# 16_ch_sample-and-hold_card_-_2.net
KiCad netlist of a schematic drawn in EAGLE
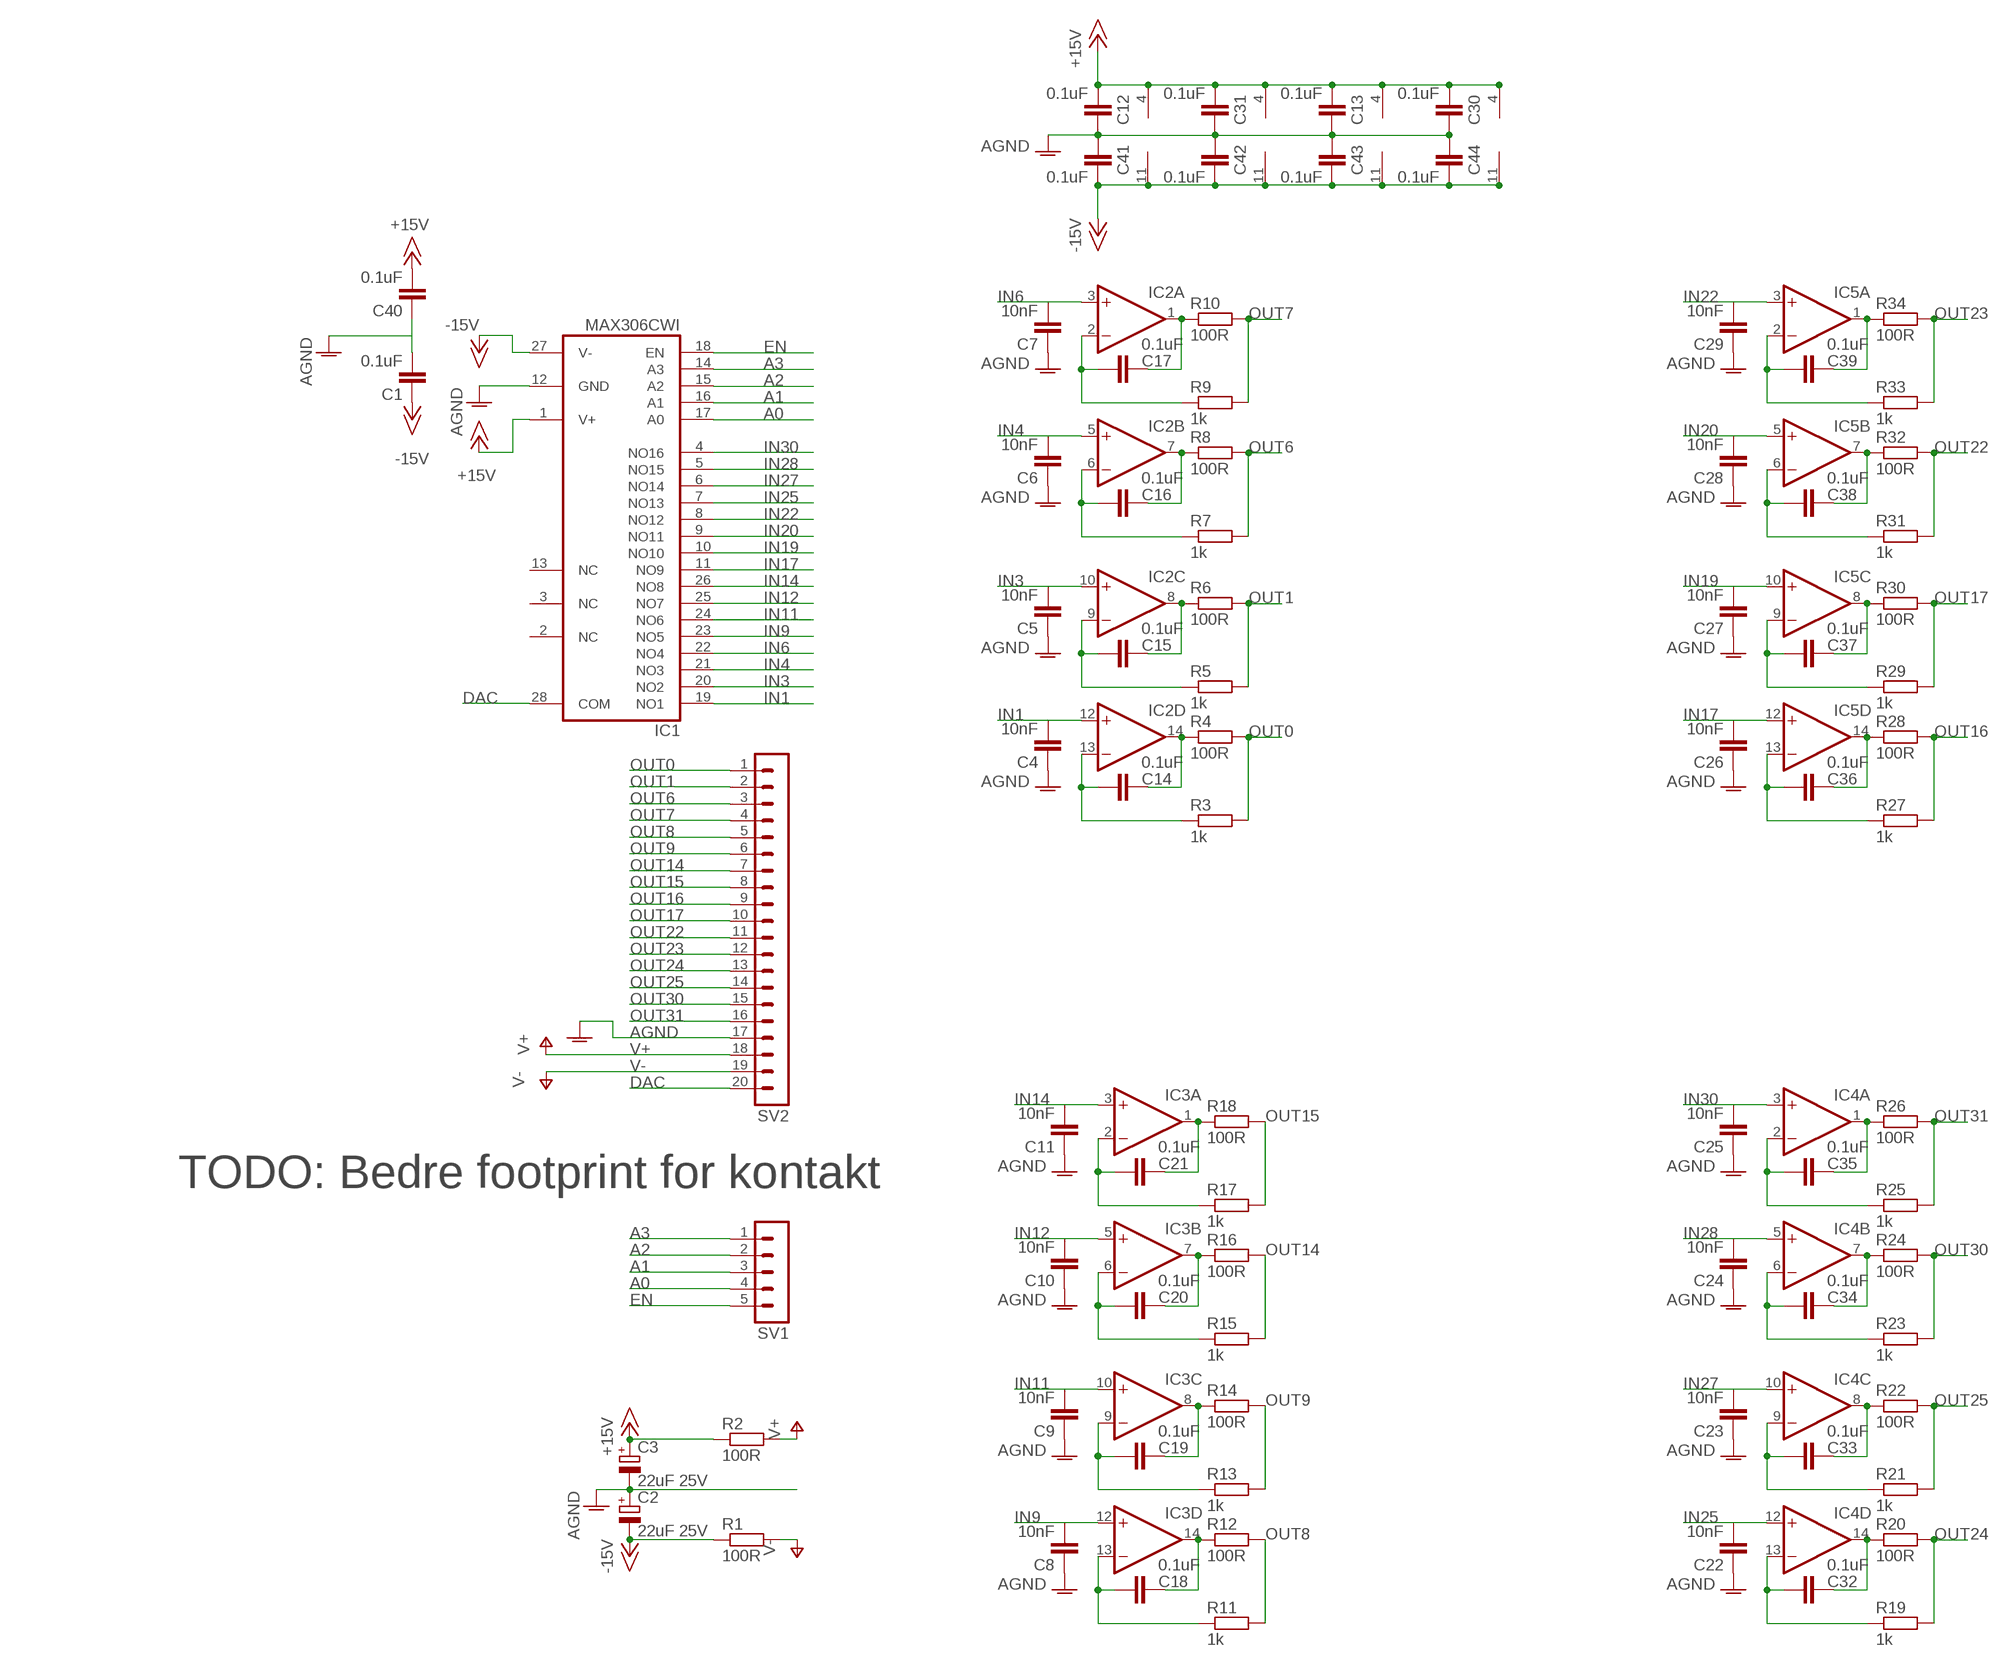
[diagram p0: schematic, sheet 1]

(export (version "E")
  (design (tool "Eeschema 10.0.6"))
  (components
    (comp (ref "C1")
      (value "0.1uF")
      (footprint "eagle-import:C0603")
      (libsource (lib "eagle-import") (part "C-EUC0603"))
    )
    (comp (ref "C2")
      (value "22uF 25V")
      (footprint "eagle-import:E2-5")
      (libsource (lib "eagle-import") (part "CPOL-EUE2-5"))
    )
    (comp (ref "C3")
      (value "22uF 25V")
      (footprint "eagle-import:E2-5")
      (libsource (lib "eagle-import") (part "CPOL-EUE2-5"))
    )
    (comp (ref "C4")
      (value "10nF")
      (footprint "eagle-import:C1206")
      (libsource (lib "eagle-import") (part "C-EUC1206"))
    )
    (comp (ref "C5")
      (value "10nF")
      (footprint "eagle-import:C1206")
      (libsource (lib "eagle-import") (part "C-EUC1206"))
    )
    (comp (ref "C6")
      (value "10nF")
      (footprint "eagle-import:C1206")
      (libsource (lib "eagle-import") (part "C-EUC1206"))
    )
    (comp (ref "C7")
      (value "10nF")
      (footprint "eagle-import:C1206")
      (libsource (lib "eagle-import") (part "C-EUC1206"))
    )
    (comp (ref "C8")
      (value "10nF")
      (footprint "eagle-import:C1206")
      (libsource (lib "eagle-import") (part "C-EUC1206"))
    )
    (comp (ref "C9")
      (value "10nF")
      (footprint "eagle-import:C1206")
      (libsource (lib "eagle-import") (part "C-EUC1206"))
    )
    (comp (ref "C10")
      (value "10nF")
      (footprint "eagle-import:C1206")
      (libsource (lib "eagle-import") (part "C-EUC1206"))
    )
    (comp (ref "C11")
      (value "10nF")
      (footprint "eagle-import:C1206")
      (libsource (lib "eagle-import") (part "C-EUC1206"))
    )
    (comp (ref "C12")
      (value "0.1uF")
      (footprint "eagle-import:C0603")
      (libsource (lib "eagle-import") (part "C-EUC0603"))
    )
    (comp (ref "C13")
      (value "0.1uF")
      (footprint "eagle-import:C0603")
      (libsource (lib "eagle-import") (part "C-EUC0603"))
    )
    (comp (ref "C14")
      (value "0.1uF")
      (footprint "eagle-import:C0603")
      (libsource (lib "eagle-import") (part "C-EUC0603"))
    )
    (comp (ref "C15")
      (value "0.1uF")
      (footprint "eagle-import:C0603")
      (libsource (lib "eagle-import") (part "C-EUC0603"))
    )
    (comp (ref "C16")
      (value "0.1uF")
      (footprint "eagle-import:C0603")
      (libsource (lib "eagle-import") (part "C-EUC0603"))
    )
    (comp (ref "C17")
      (value "0.1uF")
      (footprint "eagle-import:C0603")
      (libsource (lib "eagle-import") (part "C-EUC0603"))
    )
    (comp (ref "C18")
      (value "0.1uF")
      (footprint "eagle-import:C0603")
      (libsource (lib "eagle-import") (part "C-EUC0603"))
    )
    (comp (ref "C19")
      (value "0.1uF")
      (footprint "eagle-import:C0603")
      (libsource (lib "eagle-import") (part "C-EUC0603"))
    )
    (comp (ref "C20")
      (value "0.1uF")
      (footprint "eagle-import:C0603")
      (libsource (lib "eagle-import") (part "C-EUC0603"))
    )
    (comp (ref "C21")
      (value "0.1uF")
      (footprint "eagle-import:C0603")
      (libsource (lib "eagle-import") (part "C-EUC0603"))
    )
    (comp (ref "C22")
      (value "10nF")
      (footprint "eagle-import:C1206")
      (libsource (lib "eagle-import") (part "C-EUC1206"))
    )
    (comp (ref "C23")
      (value "10nF")
      (footprint "eagle-import:C1206")
      (libsource (lib "eagle-import") (part "C-EUC1206"))
    )
    (comp (ref "C24")
      (value "10nF")
      (footprint "eagle-import:C1206")
      (libsource (lib "eagle-import") (part "C-EUC1206"))
    )
    (comp (ref "C25")
      (value "10nF")
      (footprint "eagle-import:C1206")
      (libsource (lib "eagle-import") (part "C-EUC1206"))
    )
    (comp (ref "C26")
      (value "10nF")
      (footprint "eagle-import:C1206")
      (libsource (lib "eagle-import") (part "C-EUC1206"))
    )
    (comp (ref "C27")
      (value "10nF")
      (footprint "eagle-import:C1206")
      (libsource (lib "eagle-import") (part "C-EUC1206"))
    )
    (comp (ref "C28")
      (value "10nF")
      (footprint "eagle-import:C1206")
      (libsource (lib "eagle-import") (part "C-EUC1206"))
    )
    (comp (ref "C29")
      (value "10nF")
      (footprint "eagle-import:C1206")
      (libsource (lib "eagle-import") (part "C-EUC1206"))
    )
    (comp (ref "C30")
      (value "0.1uF")
      (footprint "eagle-import:C0603")
      (libsource (lib "eagle-import") (part "C-EUC0603"))
    )
    (comp (ref "C31")
      (value "0.1uF")
      (footprint "eagle-import:C0603")
      (libsource (lib "eagle-import") (part "C-EUC0603"))
    )
    (comp (ref "C32")
      (value "0.1uF")
      (footprint "eagle-import:C0603")
      (libsource (lib "eagle-import") (part "C-EUC0603"))
    )
    (comp (ref "C33")
      (value "0.1uF")
      (footprint "eagle-import:C0603")
      (libsource (lib "eagle-import") (part "C-EUC0603"))
    )
    (comp (ref "C34")
      (value "0.1uF")
      (footprint "eagle-import:C0603")
      (libsource (lib "eagle-import") (part "C-EUC0603"))
    )
    (comp (ref "C35")
      (value "0.1uF")
      (footprint "eagle-import:C0603")
      (libsource (lib "eagle-import") (part "C-EUC0603"))
    )
    (comp (ref "C36")
      (value "0.1uF")
      (footprint "eagle-import:C0603")
      (libsource (lib "eagle-import") (part "C-EUC0603"))
    )
    (comp (ref "C37")
      (value "0.1uF")
      (footprint "eagle-import:C0603")
      (libsource (lib "eagle-import") (part "C-EUC0603"))
    )
    (comp (ref "C38")
      (value "0.1uF")
      (footprint "eagle-import:C0603")
      (libsource (lib "eagle-import") (part "C-EUC0603"))
    )
    (comp (ref "C39")
      (value "0.1uF")
      (footprint "eagle-import:C0603")
      (libsource (lib "eagle-import") (part "C-EUC0603"))
    )
    (comp (ref "C40")
      (value "0.1uF")
      (footprint "eagle-import:C0603")
      (libsource (lib "eagle-import") (part "C-EUC0603"))
    )
    (comp (ref "C41")
      (value "0.1uF")
      (footprint "eagle-import:C0603")
      (libsource (lib "eagle-import") (part "C-EUC0603"))
    )
    (comp (ref "C42")
      (value "0.1uF")
      (footprint "eagle-import:C0603")
      (libsource (lib "eagle-import") (part "C-EUC0603"))
    )
    (comp (ref "C43")
      (value "0.1uF")
      (footprint "eagle-import:C0603")
      (libsource (lib "eagle-import") (part "C-EUC0603"))
    )
    (comp (ref "C44")
      (value "0.1uF")
      (footprint "eagle-import:C0603")
      (libsource (lib "eagle-import") (part "C-EUC0603"))
    )
    (comp (ref "IC1")
      (value "MAX306CWI")
      (footprint "eagle-import:SO28L")
      (fields (field (name "MF") "MAXIM"))
      (libsource (lib "eagle-import") (part "MAX306CWI"))
    )
    (comp (ref "IC2")
      (value "TL074D")
      (footprint "eagle-import:SO14")
      (libsource (lib "eagle-import") (part "TL074D"))
    )
    (comp (ref "IC3")
      (value "TL074D")
      (footprint "eagle-import:SO14")
      (libsource (lib "eagle-import") (part "TL074D"))
    )
    (comp (ref "IC4")
      (value "TL074D")
      (footprint "eagle-import:SO14")
      (libsource (lib "eagle-import") (part "TL074D"))
    )
    (comp (ref "IC5")
      (value "TL074D")
      (footprint "eagle-import:SO14")
      (libsource (lib "eagle-import") (part "TL074D"))
    )
    (comp (ref "R1")
      (value "100R")
      (footprint "eagle-import:0207_7")
      (libsource (lib "eagle-import") (part "R-EU_0207/7"))
    )
    (comp (ref "R2")
      (value "100R")
      (footprint "eagle-import:0207_7")
      (libsource (lib "eagle-import") (part "R-EU_0207/7"))
    )
    (comp (ref "R3")
      (value "1k")
      (footprint "eagle-import:R0603")
      (libsource (lib "eagle-import") (part "R-EU_R0603"))
    )
    (comp (ref "R4")
      (value "100R")
      (footprint "eagle-import:R0603")
      (libsource (lib "eagle-import") (part "R-EU_R0603"))
    )
    (comp (ref "R5")
      (value "1k")
      (footprint "eagle-import:R0603")
      (libsource (lib "eagle-import") (part "R-EU_R0603"))
    )
    (comp (ref "R6")
      (value "100R")
      (footprint "eagle-import:R0603")
      (libsource (lib "eagle-import") (part "R-EU_R0603"))
    )
    (comp (ref "R7")
      (value "1k")
      (footprint "eagle-import:R0603")
      (libsource (lib "eagle-import") (part "R-EU_R0603"))
    )
    (comp (ref "R8")
      (value "100R")
      (footprint "eagle-import:R0603")
      (libsource (lib "eagle-import") (part "R-EU_R0603"))
    )
    (comp (ref "R9")
      (value "1k")
      (footprint "eagle-import:R0603")
      (libsource (lib "eagle-import") (part "R-EU_R0603"))
    )
    (comp (ref "R10")
      (value "100R")
      (footprint "eagle-import:R0603")
      (libsource (lib "eagle-import") (part "R-EU_R0603"))
    )
    (comp (ref "R11")
      (value "1k")
      (footprint "eagle-import:R0603")
      (libsource (lib "eagle-import") (part "R-EU_R0603"))
    )
    (comp (ref "R12")
      (value "100R")
      (footprint "eagle-import:R0603")
      (libsource (lib "eagle-import") (part "R-EU_R0603"))
    )
    (comp (ref "R13")
      (value "1k")
      (footprint "eagle-import:R0603")
      (libsource (lib "eagle-import") (part "R-EU_R0603"))
    )
    (comp (ref "R14")
      (value "100R")
      (footprint "eagle-import:R0603")
      (libsource (lib "eagle-import") (part "R-EU_R0603"))
    )
    (comp (ref "R15")
      (value "1k")
      (footprint "eagle-import:R0603")
      (libsource (lib "eagle-import") (part "R-EU_R0603"))
    )
    (comp (ref "R16")
      (value "100R")
      (footprint "eagle-import:R0603")
      (libsource (lib "eagle-import") (part "R-EU_R0603"))
    )
    (comp (ref "R17")
      (value "1k")
      (footprint "eagle-import:R0603")
      (libsource (lib "eagle-import") (part "R-EU_R0603"))
    )
    (comp (ref "R18")
      (value "100R")
      (footprint "eagle-import:R0603")
      (libsource (lib "eagle-import") (part "R-EU_R0603"))
    )
    (comp (ref "R19")
      (value "1k")
      (footprint "eagle-import:R0603")
      (libsource (lib "eagle-import") (part "R-EU_R0603"))
    )
    (comp (ref "R20")
      (value "100R")
      (footprint "eagle-import:R0603")
      (libsource (lib "eagle-import") (part "R-EU_R0603"))
    )
    (comp (ref "R21")
      (value "1k")
      (footprint "eagle-import:R0603")
      (libsource (lib "eagle-import") (part "R-EU_R0603"))
    )
    (comp (ref "R22")
      (value "100R")
      (footprint "eagle-import:R0603")
      (libsource (lib "eagle-import") (part "R-EU_R0603"))
    )
    (comp (ref "R23")
      (value "1k")
      (footprint "eagle-import:R0603")
      (libsource (lib "eagle-import") (part "R-EU_R0603"))
    )
    (comp (ref "R24")
      (value "100R")
      (footprint "eagle-import:R0603")
      (libsource (lib "eagle-import") (part "R-EU_R0603"))
    )
    (comp (ref "R25")
      (value "1k")
      (footprint "eagle-import:R0603")
      (libsource (lib "eagle-import") (part "R-EU_R0603"))
    )
    (comp (ref "R26")
      (value "100R")
      (footprint "eagle-import:R0603")
      (libsource (lib "eagle-import") (part "R-EU_R0603"))
    )
    (comp (ref "R27")
      (value "1k")
      (footprint "eagle-import:R0603")
      (libsource (lib "eagle-import") (part "R-EU_R0603"))
    )
    (comp (ref "R28")
      (value "100R")
      (footprint "eagle-import:R0603")
      (libsource (lib "eagle-import") (part "R-EU_R0603"))
    )
    (comp (ref "R29")
      (value "1k")
      (footprint "eagle-import:R0603")
      (libsource (lib "eagle-import") (part "R-EU_R0603"))
    )
    (comp (ref "R30")
      (value "100R")
      (footprint "eagle-import:R0603")
      (libsource (lib "eagle-import") (part "R-EU_R0603"))
    )
    (comp (ref "R31")
      (value "1k")
      (footprint "eagle-import:R0603")
      (libsource (lib "eagle-import") (part "R-EU_R0603"))
    )
    (comp (ref "R32")
      (value "100R")
      (footprint "eagle-import:R0603")
      (libsource (lib "eagle-import") (part "R-EU_R0603"))
    )
    (comp (ref "R33")
      (value "1k")
      (footprint "eagle-import:R0603")
      (libsource (lib "eagle-import") (part "R-EU_R0603"))
    )
    (comp (ref "R34")
      (value "100R")
      (footprint "eagle-import:R0603")
      (libsource (lib "eagle-import") (part "R-EU_R0603"))
    )
    (comp (ref "SV1")
      (value "MA05-1")
      (footprint "eagle-import:MA05-1")
      (libsource (lib "eagle-import") (part "MA05-1"))
    )
    (comp (ref "SV2")
      (value "MA20-1")
      (footprint "eagle-import:MA20-1")
      (libsource (lib "eagle-import") (part "MA20-1"))
    )
  )
  (nets
    (net (code "1") (name "+15V") (class "Default")
      (node (ref "C12") (pin "1") (pinfunction "1_1") (pintype "passive"))
      (node (ref "C13") (pin "1") (pinfunction "1_1") (pintype "passive"))
      (node (ref "C3") (pin "+") (pinfunction "+_+") (pintype "passive"))
      (node (ref "C30") (pin "1") (pinfunction "1_1") (pintype "passive"))
      (node (ref "C31") (pin "1") (pinfunction "1_1") (pintype "passive"))
      (node (ref "C40") (pin "2") (pinfunction "2_2") (pintype "passive"))
      (node (ref "IC1") (pin "1") (pinfunction "V+_1") (pintype "power_in"))
      (node (ref "IC2") (pin "4") (pinfunction "V+_4") (pintype "power_in"))
      (node (ref "IC3") (pin "4") (pinfunction "V+_4") (pintype "power_in"))
      (node (ref "IC4") (pin "4") (pinfunction "V+_4") (pintype "power_in"))
      (node (ref "IC5") (pin "4") (pinfunction "V+_4") (pintype "power_in"))
      (node (ref "R2") (pin "1") (pinfunction "1_1") (pintype "passive"))
    )
    (net (code "2") (name "-15V") (class "Default")
      (node (ref "C1") (pin "1") (pinfunction "1_1") (pintype "passive"))
      (node (ref "C2") (pin "-") (pinfunction "-_-") (pintype "passive"))
      (node (ref "C41") (pin "2") (pinfunction "2_2") (pintype "passive"))
      (node (ref "C42") (pin "2") (pinfunction "2_2") (pintype "passive"))
      (node (ref "C43") (pin "2") (pinfunction "2_2") (pintype "passive"))
      (node (ref "C44") (pin "2") (pinfunction "2_2") (pintype "passive"))
      (node (ref "IC1") (pin "27") (pinfunction "V-_27") (pintype "power_in"))
      (node (ref "IC2") (pin "11") (pinfunction "V-_11") (pintype "power_in"))
      (node (ref "IC3") (pin "11") (pinfunction "V-_11") (pintype "power_in"))
      (node (ref "IC4") (pin "11") (pinfunction "V-_11") (pintype "power_in"))
      (node (ref "IC5") (pin "11") (pinfunction "V-_11") (pintype "power_in"))
      (node (ref "R1") (pin "1") (pinfunction "1_1") (pintype "passive"))
    )
    (net (code "3") (name "/A0") (class "Default")
      (node (ref "IC1") (pin "17") (pinfunction "A0_17") (pintype "input"))
      (node (ref "SV1") (pin "4") (pinfunction "4_4") (pintype "passive"))
    )
    (net (code "4") (name "/A1") (class "Default")
      (node (ref "IC1") (pin "16") (pinfunction "A1_16") (pintype "input"))
      (node (ref "SV1") (pin "3") (pinfunction "3_3") (pintype "passive"))
    )
    (net (code "5") (name "/A2") (class "Default")
      (node (ref "IC1") (pin "15") (pinfunction "A2_15") (pintype "input"))
      (node (ref "SV1") (pin "2") (pinfunction "2_2") (pintype "passive"))
    )
    (net (code "6") (name "/A3") (class "Default")
      (node (ref "IC1") (pin "14") (pinfunction "A3_14") (pintype "input"))
      (node (ref "SV1") (pin "1") (pinfunction "1_1") (pintype "passive"))
    )
    (net (code "7") (name "/DAC") (class "Default")
      (node (ref "IC1") (pin "28") (pinfunction "COM_28") (pintype "passive"))
      (node (ref "SV2") (pin "20") (pinfunction "20_20") (pintype "passive"))
    )
    (net (code "8") (name "/EN") (class "Default")
      (node (ref "IC1") (pin "18") (pinfunction "EN_18") (pintype "input"))
      (node (ref "SV1") (pin "5") (pinfunction "5_5") (pintype "passive"))
    )
    (net (code "9") (name "/IN1") (class "Default")
      (node (ref "C4") (pin "2") (pinfunction "2_2") (pintype "passive"))
      (node (ref "IC1") (pin "19") (pinfunction "NO1_19") (pintype "passive"))
      (node (ref "IC2") (pin "12") (pinfunction "+IN_12") (pintype "input"))
    )
    (net (code "10") (name "/IN3") (class "Default")
      (node (ref "C5") (pin "2") (pinfunction "2_2") (pintype "passive"))
      (node (ref "IC1") (pin "20") (pinfunction "NO2_20") (pintype "passive"))
      (node (ref "IC2") (pin "10") (pinfunction "+IN_10") (pintype "input"))
    )
    (net (code "11") (name "/IN4") (class "Default")
      (node (ref "C6") (pin "2") (pinfunction "2_2") (pintype "passive"))
      (node (ref "IC1") (pin "21") (pinfunction "NO3_21") (pintype "passive"))
      (node (ref "IC2") (pin "5") (pinfunction "+IN_5") (pintype "input"))
    )
    (net (code "12") (name "/IN6") (class "Default")
      (node (ref "C7") (pin "2") (pinfunction "2_2") (pintype "passive"))
      (node (ref "IC1") (pin "22") (pinfunction "NO4_22") (pintype "passive"))
      (node (ref "IC2") (pin "3") (pinfunction "+IN_3") (pintype "input"))
    )
    (net (code "13") (name "/IN9") (class "Default")
      (node (ref "C8") (pin "2") (pinfunction "2_2") (pintype "passive"))
      (node (ref "IC1") (pin "23") (pinfunction "NO5_23") (pintype "passive"))
      (node (ref "IC3") (pin "12") (pinfunction "+IN_12") (pintype "input"))
    )
    (net (code "14") (name "/IN11") (class "Default")
      (node (ref "C9") (pin "2") (pinfunction "2_2") (pintype "passive"))
      (node (ref "IC1") (pin "24") (pinfunction "NO6_24") (pintype "passive"))
      (node (ref "IC3") (pin "10") (pinfunction "+IN_10") (pintype "input"))
    )
    (net (code "15") (name "/IN12") (class "Default")
      (node (ref "C10") (pin "2") (pinfunction "2_2") (pintype "passive"))
      (node (ref "IC1") (pin "25") (pinfunction "NO7_25") (pintype "passive"))
      (node (ref "IC3") (pin "5") (pinfunction "+IN_5") (pintype "input"))
    )
    (net (code "16") (name "/IN14") (class "Default")
      (node (ref "C11") (pin "2") (pinfunction "2_2") (pintype "passive"))
      (node (ref "IC1") (pin "26") (pinfunction "NO8_26") (pintype "passive"))
      (node (ref "IC3") (pin "3") (pinfunction "+IN_3") (pintype "input"))
    )
    (net (code "17") (name "/IN17") (class "Default")
      (node (ref "C26") (pin "2") (pinfunction "2_2") (pintype "passive"))
      (node (ref "IC1") (pin "11") (pinfunction "NO9_11") (pintype "passive"))
      (node (ref "IC5") (pin "12") (pinfunction "+IN_12") (pintype "input"))
    )
    (net (code "18") (name "/IN19") (class "Default")
      (node (ref "C27") (pin "2") (pinfunction "2_2") (pintype "passive"))
      (node (ref "IC1") (pin "10") (pinfunction "NO10_10") (pintype "passive"))
      (node (ref "IC5") (pin "10") (pinfunction "+IN_10") (pintype "input"))
    )
    (net (code "19") (name "/IN20") (class "Default")
      (node (ref "C28") (pin "2") (pinfunction "2_2") (pintype "passive"))
      (node (ref "IC1") (pin "9") (pinfunction "NO11_9") (pintype "passive"))
      (node (ref "IC5") (pin "5") (pinfunction "+IN_5") (pintype "input"))
    )
    (net (code "20") (name "/IN22") (class "Default")
      (node (ref "C29") (pin "2") (pinfunction "2_2") (pintype "passive"))
      (node (ref "IC1") (pin "8") (pinfunction "NO12_8") (pintype "passive"))
      (node (ref "IC5") (pin "3") (pinfunction "+IN_3") (pintype "input"))
    )
    (net (code "21") (name "/IN25") (class "Default")
      (node (ref "C22") (pin "2") (pinfunction "2_2") (pintype "passive"))
      (node (ref "IC1") (pin "7") (pinfunction "NO13_7") (pintype "passive"))
      (node (ref "IC4") (pin "12") (pinfunction "+IN_12") (pintype "input"))
    )
    (net (code "22") (name "/IN27") (class "Default")
      (node (ref "C23") (pin "2") (pinfunction "2_2") (pintype "passive"))
      (node (ref "IC1") (pin "6") (pinfunction "NO14_6") (pintype "passive"))
      (node (ref "IC4") (pin "10") (pinfunction "+IN_10") (pintype "input"))
    )
    (net (code "23") (name "/IN28") (class "Default")
      (node (ref "C24") (pin "2") (pinfunction "2_2") (pintype "passive"))
      (node (ref "IC1") (pin "5") (pinfunction "NO15_5") (pintype "passive"))
      (node (ref "IC4") (pin "5") (pinfunction "+IN_5") (pintype "input"))
    )
    (net (code "24") (name "/IN30") (class "Default")
      (node (ref "C25") (pin "2") (pinfunction "2_2") (pintype "passive"))
      (node (ref "IC1") (pin "4") (pinfunction "NO16_4") (pintype "passive"))
      (node (ref "IC4") (pin "3") (pinfunction "+IN_3") (pintype "input"))
    )
    (net (code "25") (name "/OUT0") (class "Default")
      (node (ref "R3") (pin "2") (pinfunction "2_2") (pintype "passive"))
      (node (ref "R4") (pin "2") (pinfunction "2_2") (pintype "passive"))
      (node (ref "SV2") (pin "1") (pinfunction "1_1") (pintype "passive"))
    )
    (net (code "26") (name "/OUT1") (class "Default")
      (node (ref "R5") (pin "2") (pinfunction "2_2") (pintype "passive"))
      (node (ref "R6") (pin "2") (pinfunction "2_2") (pintype "passive"))
      (node (ref "SV2") (pin "2") (pinfunction "2_2") (pintype "passive"))
    )
    (net (code "27") (name "/OUT6") (class "Default")
      (node (ref "R7") (pin "2") (pinfunction "2_2") (pintype "passive"))
      (node (ref "R8") (pin "2") (pinfunction "2_2") (pintype "passive"))
      (node (ref "SV2") (pin "3") (pinfunction "3_3") (pintype "passive"))
    )
    (net (code "28") (name "/OUT7") (class "Default")
      (node (ref "R10") (pin "2") (pinfunction "2_2") (pintype "passive"))
      (node (ref "R9") (pin "2") (pinfunction "2_2") (pintype "passive"))
      (node (ref "SV2") (pin "4") (pinfunction "4_4") (pintype "passive"))
    )
    (net (code "29") (name "/OUT8") (class "Default")
      (node (ref "R11") (pin "2") (pinfunction "2_2") (pintype "passive"))
      (node (ref "R12") (pin "2") (pinfunction "2_2") (pintype "passive"))
      (node (ref "SV2") (pin "5") (pinfunction "5_5") (pintype "passive"))
    )
    (net (code "30") (name "/OUT9") (class "Default")
      (node (ref "R13") (pin "2") (pinfunction "2_2") (pintype "passive"))
      (node (ref "R14") (pin "2") (pinfunction "2_2") (pintype "passive"))
      (node (ref "SV2") (pin "6") (pinfunction "6_6") (pintype "passive"))
    )
    (net (code "31") (name "/OUT14") (class "Default")
      (node (ref "R15") (pin "2") (pinfunction "2_2") (pintype "passive"))
      (node (ref "R16") (pin "2") (pinfunction "2_2") (pintype "passive"))
      (node (ref "SV2") (pin "7") (pinfunction "7_7") (pintype "passive"))
    )
    (net (code "32") (name "/OUT15") (class "Default")
      (node (ref "R17") (pin "2") (pinfunction "2_2") (pintype "passive"))
      (node (ref "R18") (pin "2") (pinfunction "2_2") (pintype "passive"))
      (node (ref "SV2") (pin "8") (pinfunction "8_8") (pintype "passive"))
    )
    (net (code "33") (name "/OUT16") (class "Default")
      (node (ref "R27") (pin "2") (pinfunction "2_2") (pintype "passive"))
      (node (ref "R28") (pin "2") (pinfunction "2_2") (pintype "passive"))
      (node (ref "SV2") (pin "9") (pinfunction "9_9") (pintype "passive"))
    )
    (net (code "34") (name "/OUT17") (class "Default")
      (node (ref "R29") (pin "2") (pinfunction "2_2") (pintype "passive"))
      (node (ref "R30") (pin "2") (pinfunction "2_2") (pintype "passive"))
      (node (ref "SV2") (pin "10") (pinfunction "10_10") (pintype "passive"))
    )
    (net (code "35") (name "/OUT22") (class "Default")
      (node (ref "R31") (pin "2") (pinfunction "2_2") (pintype "passive"))
      (node (ref "R32") (pin "2") (pinfunction "2_2") (pintype "passive"))
      (node (ref "SV2") (pin "11") (pinfunction "11_11") (pintype "passive"))
    )
    (net (code "36") (name "/OUT23") (class "Default")
      (node (ref "R33") (pin "2") (pinfunction "2_2") (pintype "passive"))
      (node (ref "R34") (pin "2") (pinfunction "2_2") (pintype "passive"))
      (node (ref "SV2") (pin "12") (pinfunction "12_12") (pintype "passive"))
    )
    (net (code "37") (name "/OUT24") (class "Default")
      (node (ref "R19") (pin "2") (pinfunction "2_2") (pintype "passive"))
      (node (ref "R20") (pin "2") (pinfunction "2_2") (pintype "passive"))
      (node (ref "SV2") (pin "13") (pinfunction "13_13") (pintype "passive"))
    )
    (net (code "38") (name "/OUT25") (class "Default")
      (node (ref "R21") (pin "2") (pinfunction "2_2") (pintype "passive"))
      (node (ref "R22") (pin "2") (pinfunction "2_2") (pintype "passive"))
      (node (ref "SV2") (pin "14") (pinfunction "14_14") (pintype "passive"))
    )
    (net (code "39") (name "/OUT30") (class "Default")
      (node (ref "R23") (pin "2") (pinfunction "2_2") (pintype "passive"))
      (node (ref "R24") (pin "2") (pinfunction "2_2") (pintype "passive"))
      (node (ref "SV2") (pin "15") (pinfunction "15_15") (pintype "passive"))
    )
    (net (code "40") (name "/OUT31") (class "Default")
      (node (ref "R25") (pin "2") (pinfunction "2_2") (pintype "passive"))
      (node (ref "R26") (pin "2") (pinfunction "2_2") (pintype "passive"))
      (node (ref "SV2") (pin "16") (pinfunction "16_16") (pintype "passive"))
    )
    (net (code "41") (name "AGND") (class "Default")
      (node (ref "C1") (pin "2") (pinfunction "2_2") (pintype "passive"))
      (node (ref "C10") (pin "1") (pinfunction "1_1") (pintype "passive"))
      (node (ref "C11") (pin "1") (pinfunction "1_1") (pintype "passive"))
      (node (ref "C12") (pin "2") (pinfunction "2_2") (pintype "passive"))
      (node (ref "C13") (pin "2") (pinfunction "2_2") (pintype "passive"))
      (node (ref "C2") (pin "+") (pinfunction "+_+") (pintype "passive"))
      (node (ref "C22") (pin "1") (pinfunction "1_1") (pintype "passive"))
      (node (ref "C23") (pin "1") (pinfunction "1_1") (pintype "passive"))
      (node (ref "C24") (pin "1") (pinfunction "1_1") (pintype "passive"))
      (node (ref "C25") (pin "1") (pinfunction "1_1") (pintype "passive"))
      (node (ref "C26") (pin "1") (pinfunction "1_1") (pintype "passive"))
      (node (ref "C27") (pin "1") (pinfunction "1_1") (pintype "passive"))
      (node (ref "C28") (pin "1") (pinfunction "1_1") (pintype "passive"))
      (node (ref "C29") (pin "1") (pinfunction "1_1") (pintype "passive"))
      (node (ref "C3") (pin "-") (pinfunction "-_-") (pintype "passive"))
      (node (ref "C30") (pin "2") (pinfunction "2_2") (pintype "passive"))
      (node (ref "C31") (pin "2") (pinfunction "2_2") (pintype "passive"))
      (node (ref "C4") (pin "1") (pinfunction "1_1") (pintype "passive"))
      (node (ref "C40") (pin "1") (pinfunction "1_1") (pintype "passive"))
      (node (ref "C41") (pin "1") (pinfunction "1_1") (pintype "passive"))
      (node (ref "C42") (pin "1") (pinfunction "1_1") (pintype "passive"))
      (node (ref "C43") (pin "1") (pinfunction "1_1") (pintype "passive"))
      (node (ref "C44") (pin "1") (pinfunction "1_1") (pintype "passive"))
      (node (ref "C5") (pin "1") (pinfunction "1_1") (pintype "passive"))
      (node (ref "C6") (pin "1") (pinfunction "1_1") (pintype "passive"))
      (node (ref "C7") (pin "1") (pinfunction "1_1") (pintype "passive"))
      (node (ref "C8") (pin "1") (pinfunction "1_1") (pintype "passive"))
      (node (ref "C9") (pin "1") (pinfunction "1_1") (pintype "passive"))
      (node (ref "IC1") (pin "12") (pinfunction "GND_12") (pintype "power_in"))
      (node (ref "SV2") (pin "17") (pinfunction "17_17") (pintype "passive"))
    )
    (net (code "42") (name "Net-(IC2A--IN)") (class "Default")
      (node (ref "C17") (pin "2") (pinfunction "2_2") (pintype "passive"))
      (node (ref "IC2") (pin "2") (pinfunction "-IN_2") (pintype "input"))
      (node (ref "R9") (pin "1") (pinfunction "1_1") (pintype "passive"))
    )
    (net (code "43") (name "Net-(IC2A-OUT)") (class "Default")
      (node (ref "C17") (pin "1") (pinfunction "1_1") (pintype "passive"))
      (node (ref "IC2") (pin "1") (pinfunction "OUT_1") (pintype "output"))
      (node (ref "R10") (pin "1") (pinfunction "1_1") (pintype "passive"))
    )
    (net (code "44") (name "Net-(IC2B--IN)") (class "Default")
      (node (ref "C16") (pin "2") (pinfunction "2_2") (pintype "passive"))
      (node (ref "IC2") (pin "6") (pinfunction "-IN_6") (pintype "input"))
      (node (ref "R7") (pin "1") (pinfunction "1_1") (pintype "passive"))
    )
    (net (code "45") (name "Net-(IC2B-OUT)") (class "Default")
      (node (ref "C16") (pin "1") (pinfunction "1_1") (pintype "passive"))
      (node (ref "IC2") (pin "7") (pinfunction "OUT_7") (pintype "output"))
      (node (ref "R8") (pin "1") (pinfunction "1_1") (pintype "passive"))
    )
    (net (code "46") (name "Net-(IC2C--IN)") (class "Default")
      (node (ref "C15") (pin "2") (pinfunction "2_2") (pintype "passive"))
      (node (ref "IC2") (pin "9") (pinfunction "-IN_9") (pintype "input"))
      (node (ref "R5") (pin "1") (pinfunction "1_1") (pintype "passive"))
    )
    (net (code "47") (name "Net-(IC2C-OUT)") (class "Default")
      (node (ref "C15") (pin "1") (pinfunction "1_1") (pintype "passive"))
      (node (ref "IC2") (pin "8") (pinfunction "OUT_8") (pintype "output"))
      (node (ref "R6") (pin "1") (pinfunction "1_1") (pintype "passive"))
    )
    (net (code "48") (name "Net-(IC2D--IN)") (class "Default")
      (node (ref "C14") (pin "2") (pinfunction "2_2") (pintype "passive"))
      (node (ref "IC2") (pin "13") (pinfunction "-IN_13") (pintype "input"))
      (node (ref "R3") (pin "1") (pinfunction "1_1") (pintype "passive"))
    )
    (net (code "49") (name "Net-(IC2D-OUT)") (class "Default")
      (node (ref "C14") (pin "1") (pinfunction "1_1") (pintype "passive"))
      (node (ref "IC2") (pin "14") (pinfunction "OUT_14") (pintype "output"))
      (node (ref "R4") (pin "1") (pinfunction "1_1") (pintype "passive"))
    )
    (net (code "50") (name "Net-(IC3A--IN)") (class "Default")
      (node (ref "C21") (pin "2") (pinfunction "2_2") (pintype "passive"))
      (node (ref "IC3") (pin "2") (pinfunction "-IN_2") (pintype "input"))
      (node (ref "R17") (pin "1") (pinfunction "1_1") (pintype "passive"))
    )
    (net (code "51") (name "Net-(IC3A-OUT)") (class "Default")
      (node (ref "C21") (pin "1") (pinfunction "1_1") (pintype "passive"))
      (node (ref "IC3") (pin "1") (pinfunction "OUT_1") (pintype "output"))
      (node (ref "R18") (pin "1") (pinfunction "1_1") (pintype "passive"))
    )
    (net (code "52") (name "Net-(IC3B--IN)") (class "Default")
      (node (ref "C20") (pin "2") (pinfunction "2_2") (pintype "passive"))
      (node (ref "IC3") (pin "6") (pinfunction "-IN_6") (pintype "input"))
      (node (ref "R15") (pin "1") (pinfunction "1_1") (pintype "passive"))
    )
    (net (code "53") (name "Net-(IC3B-OUT)") (class "Default")
      (node (ref "C20") (pin "1") (pinfunction "1_1") (pintype "passive"))
      (node (ref "IC3") (pin "7") (pinfunction "OUT_7") (pintype "output"))
      (node (ref "R16") (pin "1") (pinfunction "1_1") (pintype "passive"))
    )
    (net (code "54") (name "Net-(IC3C--IN)") (class "Default")
      (node (ref "C19") (pin "2") (pinfunction "2_2") (pintype "passive"))
      (node (ref "IC3") (pin "9") (pinfunction "-IN_9") (pintype "input"))
      (node (ref "R13") (pin "1") (pinfunction "1_1") (pintype "passive"))
    )
    (net (code "55") (name "Net-(IC3C-OUT)") (class "Default")
      (node (ref "C19") (pin "1") (pinfunction "1_1") (pintype "passive"))
      (node (ref "IC3") (pin "8") (pinfunction "OUT_8") (pintype "output"))
      (node (ref "R14") (pin "1") (pinfunction "1_1") (pintype "passive"))
    )
    (net (code "56") (name "Net-(IC3D--IN)") (class "Default")
      (node (ref "C18") (pin "2") (pinfunction "2_2") (pintype "passive"))
      (node (ref "IC3") (pin "13") (pinfunction "-IN_13") (pintype "input"))
      (node (ref "R11") (pin "1") (pinfunction "1_1") (pintype "passive"))
    )
    (net (code "57") (name "Net-(IC3D-OUT)") (class "Default")
      (node (ref "C18") (pin "1") (pinfunction "1_1") (pintype "passive"))
      (node (ref "IC3") (pin "14") (pinfunction "OUT_14") (pintype "output"))
      (node (ref "R12") (pin "1") (pinfunction "1_1") (pintype "passive"))
    )
    (net (code "58") (name "Net-(IC4A--IN)") (class "Default")
      (node (ref "C35") (pin "2") (pinfunction "2_2") (pintype "passive"))
      (node (ref "IC4") (pin "2") (pinfunction "-IN_2") (pintype "input"))
      (node (ref "R25") (pin "1") (pinfunction "1_1") (pintype "passive"))
    )
    (net (code "59") (name "Net-(IC4A-OUT)") (class "Default")
      (node (ref "C35") (pin "1") (pinfunction "1_1") (pintype "passive"))
      (node (ref "IC4") (pin "1") (pinfunction "OUT_1") (pintype "output"))
      (node (ref "R26") (pin "1") (pinfunction "1_1") (pintype "passive"))
    )
    (net (code "60") (name "Net-(IC4B--IN)") (class "Default")
      (node (ref "C34") (pin "2") (pinfunction "2_2") (pintype "passive"))
      (node (ref "IC4") (pin "6") (pinfunction "-IN_6") (pintype "input"))
      (node (ref "R23") (pin "1") (pinfunction "1_1") (pintype "passive"))
    )
    (net (code "61") (name "Net-(IC4B-OUT)") (class "Default")
      (node (ref "C34") (pin "1") (pinfunction "1_1") (pintype "passive"))
      (node (ref "IC4") (pin "7") (pinfunction "OUT_7") (pintype "output"))
      (node (ref "R24") (pin "1") (pinfunction "1_1") (pintype "passive"))
    )
    (net (code "62") (name "Net-(IC4C--IN)") (class "Default")
      (node (ref "C33") (pin "2") (pinfunction "2_2") (pintype "passive"))
      (node (ref "IC4") (pin "9") (pinfunction "-IN_9") (pintype "input"))
      (node (ref "R21") (pin "1") (pinfunction "1_1") (pintype "passive"))
    )
    (net (code "63") (name "Net-(IC4C-OUT)") (class "Default")
      (node (ref "C33") (pin "1") (pinfunction "1_1") (pintype "passive"))
      (node (ref "IC4") (pin "8") (pinfunction "OUT_8") (pintype "output"))
      (node (ref "R22") (pin "1") (pinfunction "1_1") (pintype "passive"))
    )
    (net (code "64") (name "Net-(IC4D--IN)") (class "Default")
      (node (ref "C32") (pin "2") (pinfunction "2_2") (pintype "passive"))
      (node (ref "IC4") (pin "13") (pinfunction "-IN_13") (pintype "input"))
      (node (ref "R19") (pin "1") (pinfunction "1_1") (pintype "passive"))
    )
    (net (code "65") (name "Net-(IC4D-OUT)") (class "Default")
      (node (ref "C32") (pin "1") (pinfunction "1_1") (pintype "passive"))
      (node (ref "IC4") (pin "14") (pinfunction "OUT_14") (pintype "output"))
      (node (ref "R20") (pin "1") (pinfunction "1_1") (pintype "passive"))
    )
    (net (code "66") (name "Net-(IC5A--IN)") (class "Default")
      (node (ref "C39") (pin "2") (pinfunction "2_2") (pintype "passive"))
      (node (ref "IC5") (pin "2") (pinfunction "-IN_2") (pintype "input"))
      (node (ref "R33") (pin "1") (pinfunction "1_1") (pintype "passive"))
    )
    (net (code "67") (name "Net-(IC5A-OUT)") (class "Default")
      (node (ref "C39") (pin "1") (pinfunction "1_1") (pintype "passive"))
      (node (ref "IC5") (pin "1") (pinfunction "OUT_1") (pintype "output"))
      (node (ref "R34") (pin "1") (pinfunction "1_1") (pintype "passive"))
    )
    (net (code "68") (name "Net-(IC5B--IN)") (class "Default")
      (node (ref "C38") (pin "2") (pinfunction "2_2") (pintype "passive"))
      (node (ref "IC5") (pin "6") (pinfunction "-IN_6") (pintype "input"))
      (node (ref "R31") (pin "1") (pinfunction "1_1") (pintype "passive"))
    )
    (net (code "69") (name "Net-(IC5B-OUT)") (class "Default")
      (node (ref "C38") (pin "1") (pinfunction "1_1") (pintype "passive"))
      (node (ref "IC5") (pin "7") (pinfunction "OUT_7") (pintype "output"))
      (node (ref "R32") (pin "1") (pinfunction "1_1") (pintype "passive"))
    )
    (net (code "70") (name "Net-(IC5C--IN)") (class "Default")
      (node (ref "C37") (pin "2") (pinfunction "2_2") (pintype "passive"))
      (node (ref "IC5") (pin "9") (pinfunction "-IN_9") (pintype "input"))
      (node (ref "R29") (pin "1") (pinfunction "1_1") (pintype "passive"))
    )
    (net (code "71") (name "Net-(IC5C-OUT)") (class "Default")
      (node (ref "C37") (pin "1") (pinfunction "1_1") (pintype "passive"))
      (node (ref "IC5") (pin "8") (pinfunction "OUT_8") (pintype "output"))
      (node (ref "R30") (pin "1") (pinfunction "1_1") (pintype "passive"))
    )
    (net (code "72") (name "Net-(IC5D--IN)") (class "Default")
      (node (ref "C36") (pin "2") (pinfunction "2_2") (pintype "passive"))
      (node (ref "IC5") (pin "13") (pinfunction "-IN_13") (pintype "input"))
      (node (ref "R27") (pin "1") (pinfunction "1_1") (pintype "passive"))
    )
    (net (code "73") (name "Net-(IC5D-OUT)") (class "Default")
      (node (ref "C36") (pin "1") (pinfunction "1_1") (pintype "passive"))
      (node (ref "IC5") (pin "14") (pinfunction "OUT_14") (pintype "output"))
      (node (ref "R28") (pin "1") (pinfunction "1_1") (pintype "passive"))
    )
    (net (code "74") (name "V+") (class "Default")
      (node (ref "R2") (pin "2") (pinfunction "2_2") (pintype "passive"))
      (node (ref "SV2") (pin "18") (pinfunction "18_18") (pintype "passive"))
    )
    (net (code "75") (name "V-") (class "Default")
      (node (ref "R1") (pin "2") (pinfunction "2_2") (pintype "passive"))
      (node (ref "SV2") (pin "19") (pinfunction "19_19") (pintype "passive"))
    )
    (net (code "76") (name "unconnected-(IC1-NC-Pad2)") (class "Default")
      (node (ref "IC1") (pin "2") (pinfunction "NC_2") (pintype "no_connect"))
    )
    (net (code "77") (name "unconnected-(IC1-NC-Pad3)") (class "Default")
      (node (ref "IC1") (pin "3") (pinfunction "NC_3") (pintype "no_connect"))
    )
    (net (code "78") (name "unconnected-(IC1-NC-Pad13)") (class "Default")
      (node (ref "IC1") (pin "13") (pinfunction "NC_13") (pintype "no_connect"))
    )
  )
)
